# buttons.net
KiCad netlist of a schematic drawn in EAGLE
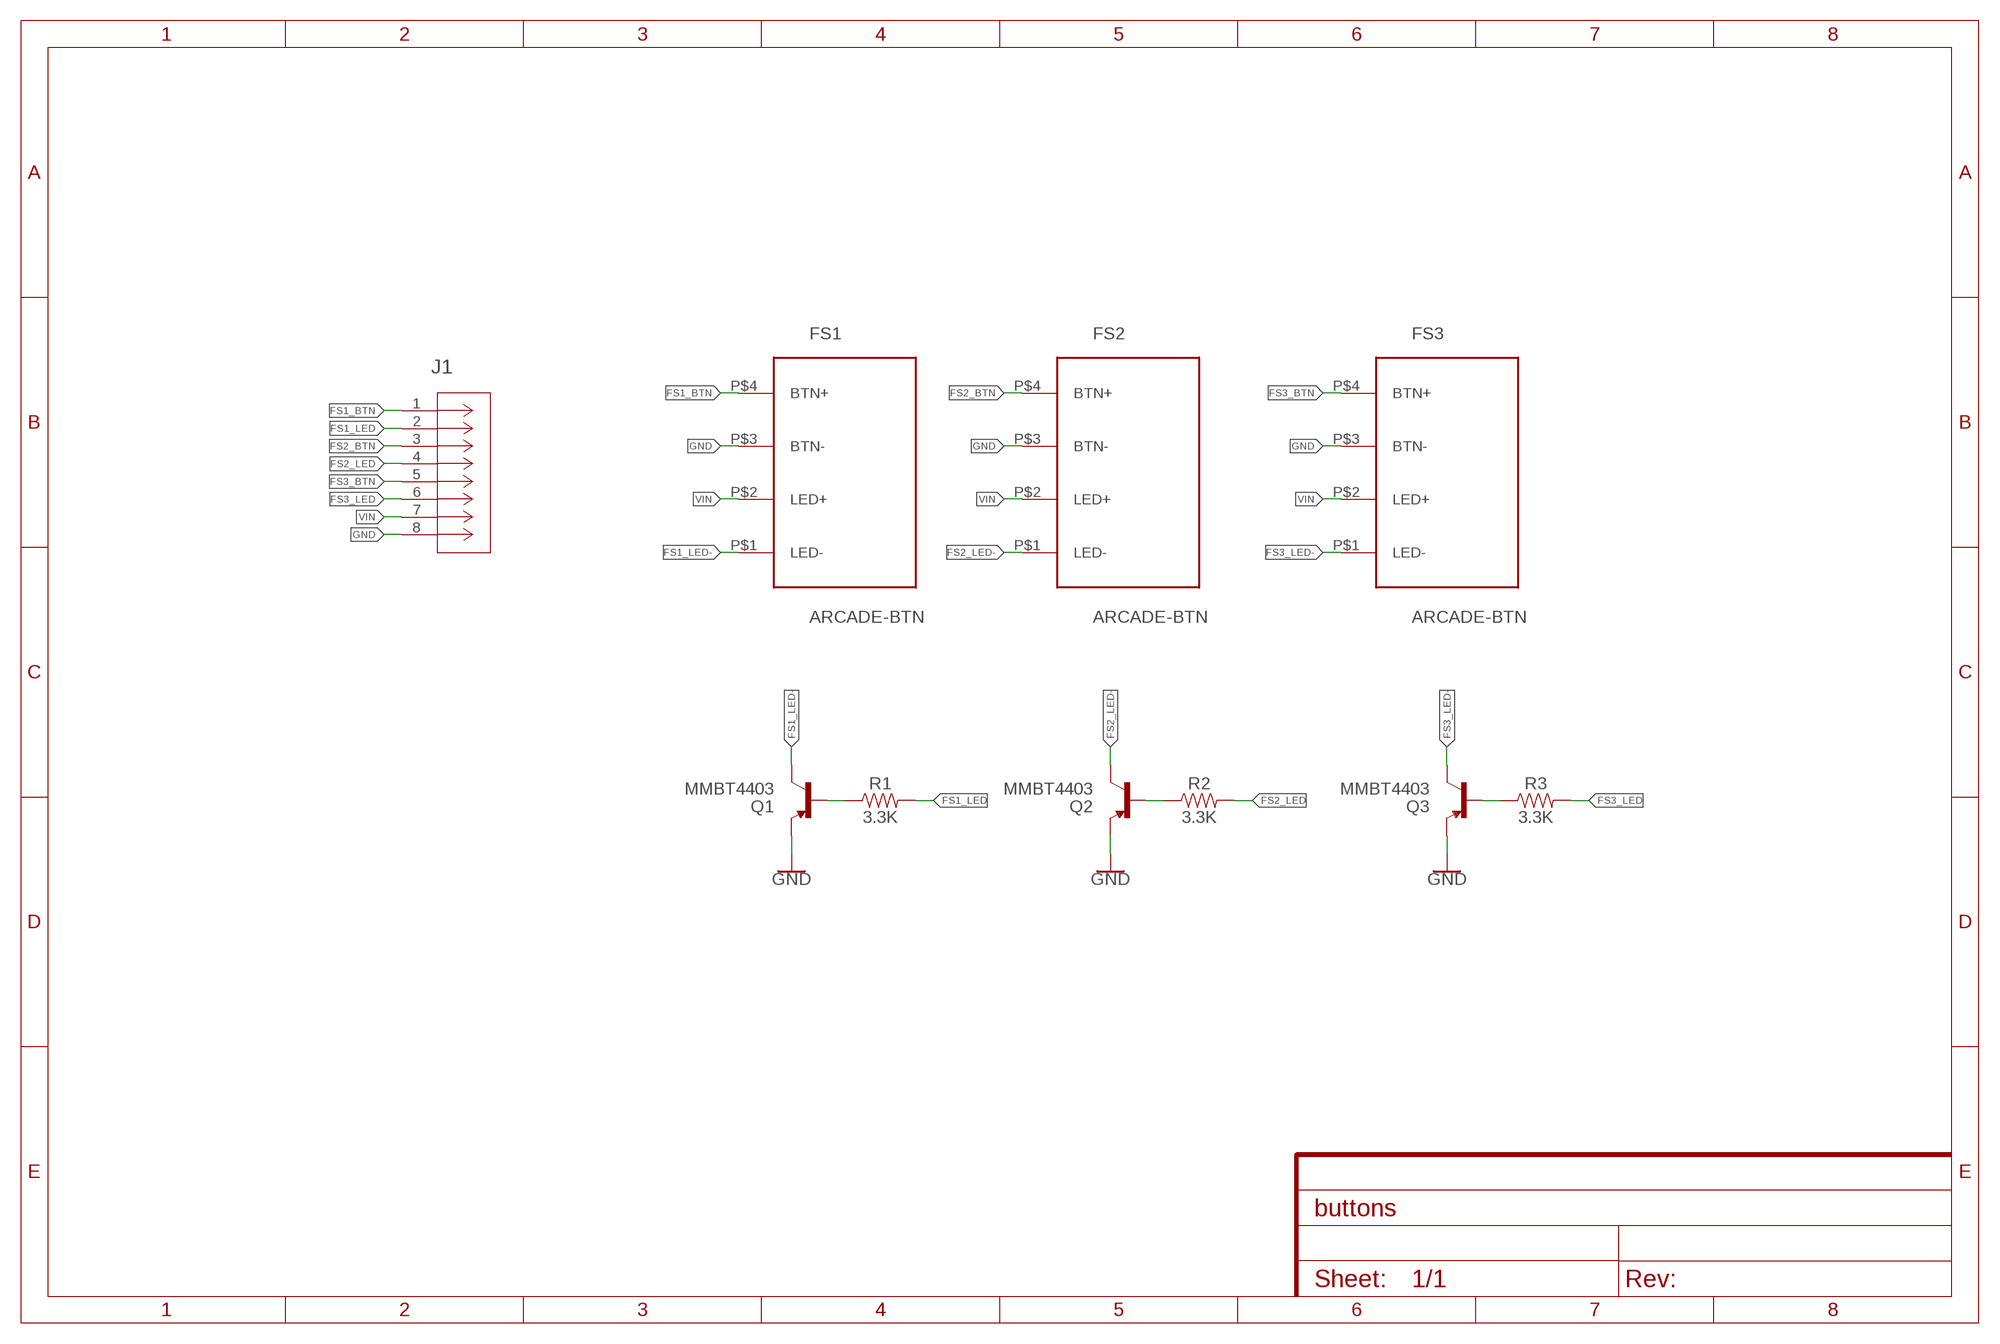
[diagram p0: schematic, sheet 1]

(export (version "E")
  (design (tool "Eeschema 10.0.6"))
  (components
    (comp (ref "FS1")
      (value "ARCADE-BTN")
      (footprint "eagle-import:ARCADE-BTN")
      (libsource (lib "eagle-import") (part "ARCADE-BTN"))
    )
    (comp (ref "FS2")
      (value "ARCADE-BTN")
      (footprint "eagle-import:ARCADE-BTN")
      (libsource (lib "eagle-import") (part "ARCADE-BTN"))
    )
    (comp (ref "FS3")
      (value "ARCADE-BTN")
      (footprint "eagle-import:ARCADE-BTN")
      (libsource (lib "eagle-import") (part "ARCADE-BTN"))
    )
    (comp (ref "J1")
      (value "188275-8")
      (footprint "eagle-import:CONN_188275-8_TYC")
      (fields (field (name "COPYRIGHT") "Copyright (C) 2016 Accelerated Designs. All rights reserved"))
      (libsource (lib "eagle-import") (part "188275-8"))
    )
    (comp (ref "Q1")
      (value "MMBT4403")
      (footprint "eagle-import:SOT23-3")
      (libsource (lib "eagle-import") (part "TRANSISTOR_PNPMMBT4403"))
    )
    (comp (ref "Q2")
      (value "MMBT4403")
      (footprint "eagle-import:SOT23-3")
      (libsource (lib "eagle-import") (part "TRANSISTOR_PNPMMBT4403"))
    )
    (comp (ref "Q3")
      (value "MMBT4403")
      (footprint "eagle-import:SOT23-3")
      (libsource (lib "eagle-import") (part "TRANSISTOR_PNPMMBT4403"))
    )
    (comp (ref "R1")
      (value "3.3K")
      (footprint "eagle-import:1206")
      (libsource (lib "eagle-import") (part "RESISTOR1206"))
    )
    (comp (ref "R2")
      (value "3.3K")
      (footprint "eagle-import:1206")
      (libsource (lib "eagle-import") (part "RESISTOR1206"))
    )
    (comp (ref "R3")
      (value "3.3K")
      (footprint "eagle-import:1206")
      (libsource (lib "eagle-import") (part "RESISTOR1206"))
    )
  )
  (nets
    (net (code "1") (name "FS1_BTN") (class "Default")
      (node (ref "FS1") (pin "P$4") (pinfunction "BTN+_P$4") (pintype "bidirectional"))
      (node (ref "J1") (pin "1") (pinfunction "1_1") (pintype "passive"))
    )
    (net (code "2") (name "FS1_LED") (class "Default")
      (node (ref "J1") (pin "2") (pinfunction "2_2") (pintype "passive"))
      (node (ref "R1") (pin "2") (pinfunction "2_2") (pintype "passive"))
    )
    (net (code "3") (name "FS1_LED-") (class "Default")
      (node (ref "FS1") (pin "P$1") (pinfunction "LED-_P$1") (pintype "bidirectional"))
      (node (ref "Q1") (pin "3") (pinfunction "C_3") (pintype "passive"))
    )
    (net (code "4") (name "FS2_BTN") (class "Default")
      (node (ref "FS2") (pin "P$4") (pinfunction "BTN+_P$4") (pintype "bidirectional"))
      (node (ref "J1") (pin "3") (pinfunction "3_3") (pintype "passive"))
    )
    (net (code "5") (name "FS2_LED") (class "Default")
      (node (ref "J1") (pin "4") (pinfunction "4_4") (pintype "passive"))
      (node (ref "R2") (pin "2") (pinfunction "2_2") (pintype "passive"))
    )
    (net (code "6") (name "FS2_LED-") (class "Default")
      (node (ref "FS2") (pin "P$1") (pinfunction "LED-_P$1") (pintype "bidirectional"))
      (node (ref "Q2") (pin "3") (pinfunction "C_3") (pintype "passive"))
    )
    (net (code "7") (name "FS3_BTN") (class "Default")
      (node (ref "FS3") (pin "P$4") (pinfunction "BTN+_P$4") (pintype "bidirectional"))
      (node (ref "J1") (pin "5") (pinfunction "5_5") (pintype "passive"))
    )
    (net (code "8") (name "FS3_LED") (class "Default")
      (node (ref "J1") (pin "6") (pinfunction "6_6") (pintype "passive"))
      (node (ref "R3") (pin "2") (pinfunction "2_2") (pintype "passive"))
    )
    (net (code "9") (name "FS3_LED-") (class "Default")
      (node (ref "FS3") (pin "P$1") (pinfunction "LED-_P$1") (pintype "bidirectional"))
      (node (ref "Q3") (pin "3") (pinfunction "C_3") (pintype "passive"))
    )
    (net (code "10") (name "GND") (class "Default")
      (node (ref "FS1") (pin "P$3") (pinfunction "BTN-_P$3") (pintype "bidirectional"))
      (node (ref "FS2") (pin "P$3") (pinfunction "BTN-_P$3") (pintype "bidirectional"))
      (node (ref "FS3") (pin "P$3") (pinfunction "BTN-_P$3") (pintype "bidirectional"))
      (node (ref "J1") (pin "8") (pinfunction "8_8") (pintype "passive"))
      (node (ref "Q1") (pin "2") (pinfunction "E_2") (pintype "passive"))
      (node (ref "Q2") (pin "2") (pinfunction "E_2") (pintype "passive"))
      (node (ref "Q3") (pin "2") (pinfunction "E_2") (pintype "passive"))
    )
    (net (code "11") (name "Net-(Q1-B)") (class "Default")
      (node (ref "Q1") (pin "1") (pinfunction "B_1") (pintype "passive"))
      (node (ref "R1") (pin "1") (pinfunction "1_1") (pintype "passive"))
    )
    (net (code "12") (name "Net-(Q2-B)") (class "Default")
      (node (ref "Q2") (pin "1") (pinfunction "B_1") (pintype "passive"))
      (node (ref "R2") (pin "1") (pinfunction "1_1") (pintype "passive"))
    )
    (net (code "13") (name "Net-(Q3-B)") (class "Default")
      (node (ref "Q3") (pin "1") (pinfunction "B_1") (pintype "passive"))
      (node (ref "R3") (pin "1") (pinfunction "1_1") (pintype "passive"))
    )
    (net (code "14") (name "VIN") (class "Default")
      (node (ref "FS1") (pin "P$2") (pinfunction "LED+_P$2") (pintype "bidirectional"))
      (node (ref "FS2") (pin "P$2") (pinfunction "LED+_P$2") (pintype "bidirectional"))
      (node (ref "FS3") (pin "P$2") (pinfunction "LED+_P$2") (pintype "bidirectional"))
      (node (ref "J1") (pin "7") (pinfunction "7_7") (pintype "passive"))
    )
  )
)
